# LAMEBOY.net
KiCad netlist of a schematic drawn in EAGLE
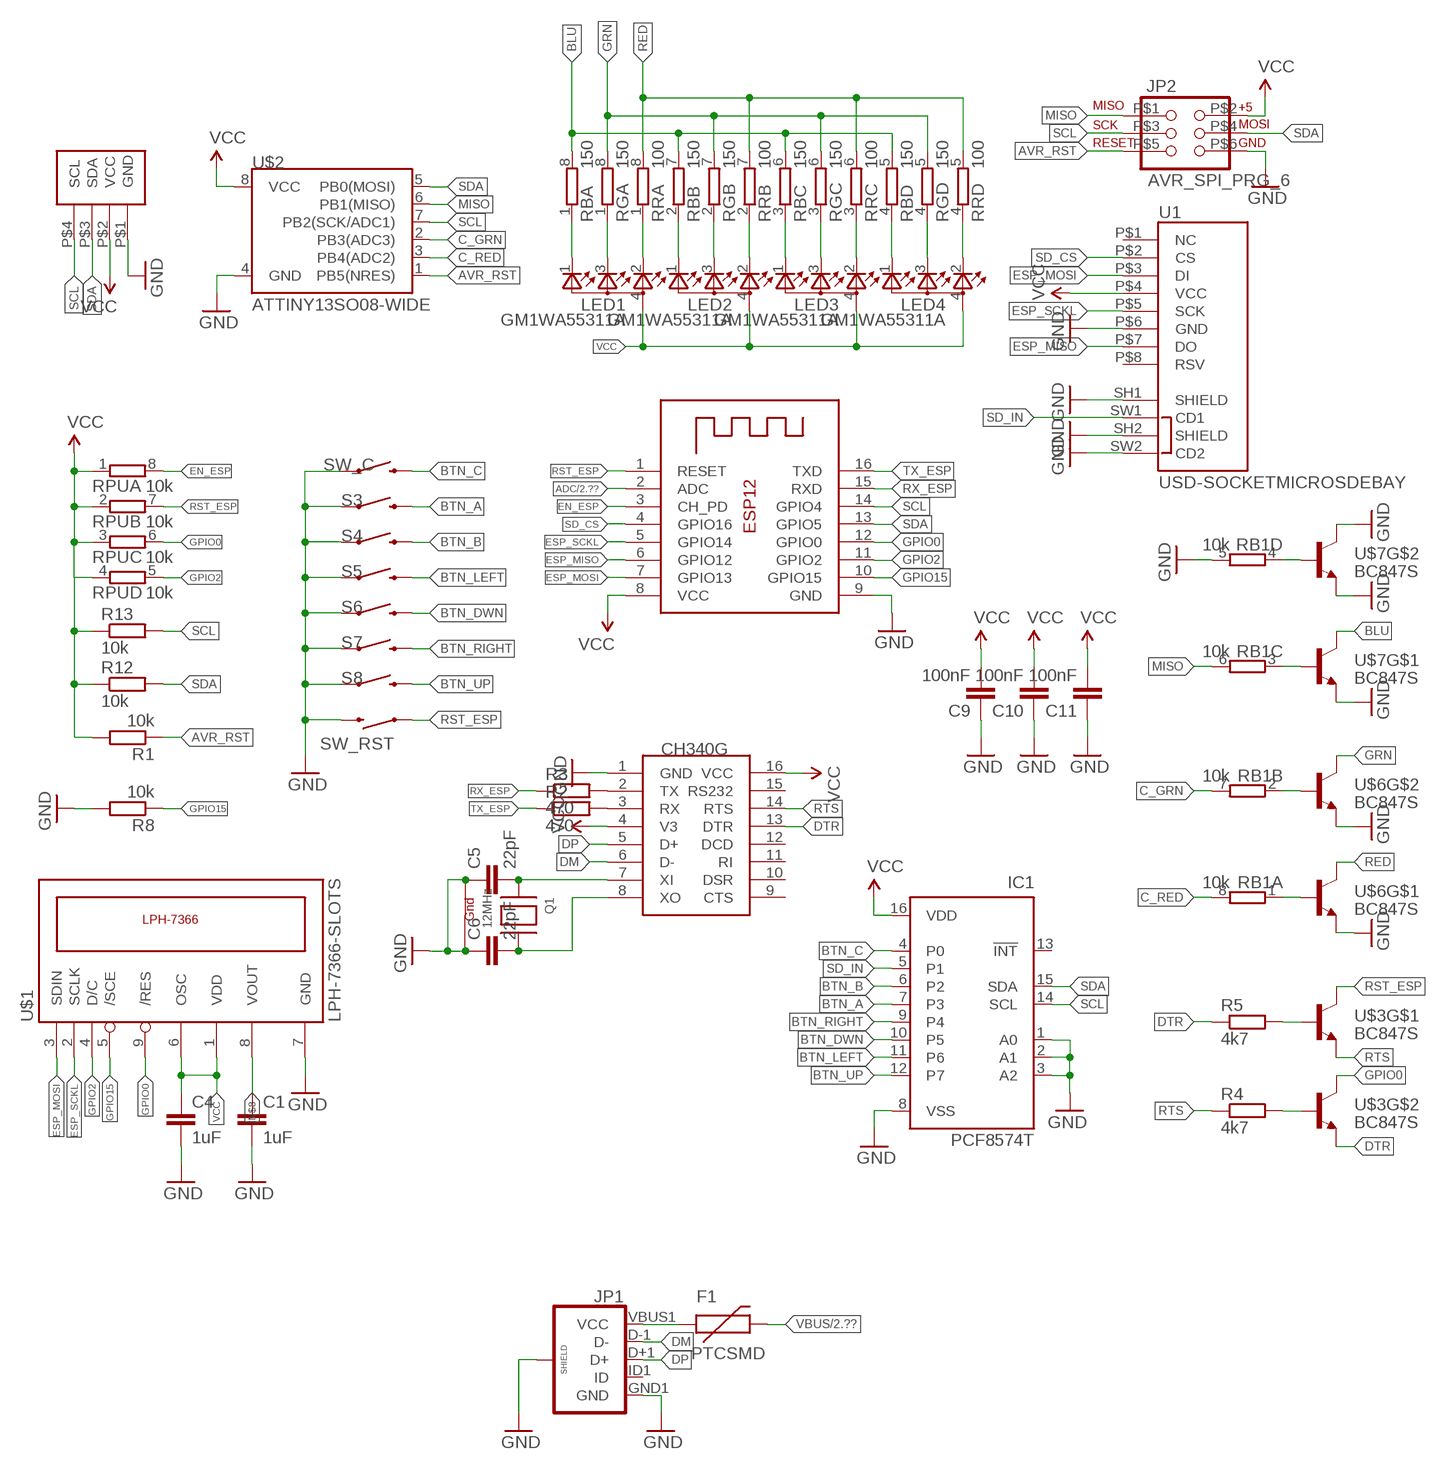
[diagram p0: schematic, sheet 1]
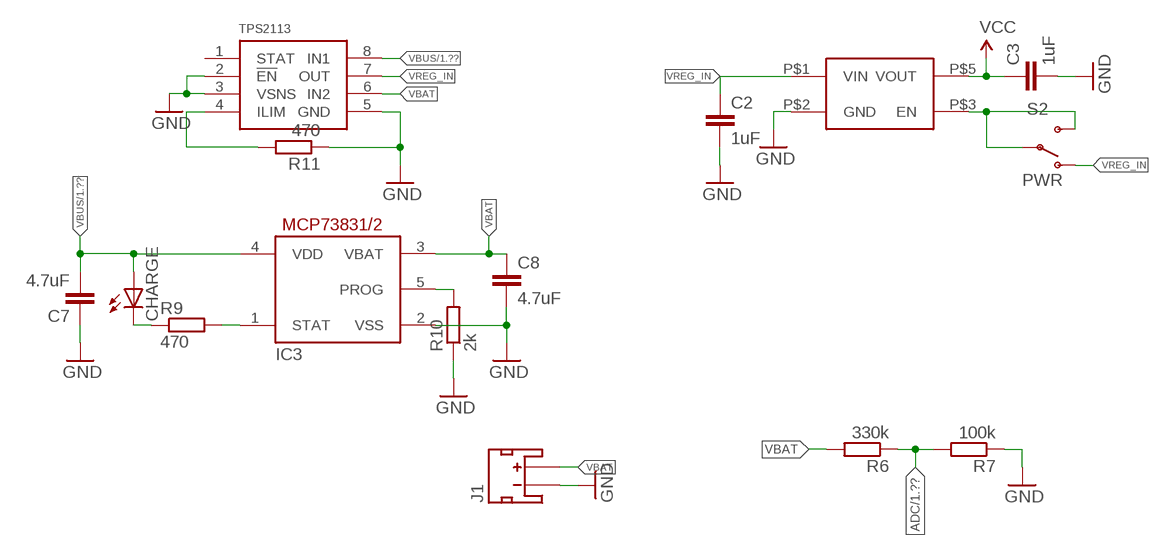
[diagram p1: schematic, sheet 2]

(export (version "E")
  (design (tool "Eeschema 10.0.6"))
  (components
    (comp (ref "C2")
      (value "1uF")
      (footprint "eagle-import:ONEFITSALL")
      (libsource (lib "eagle-import") (part "C-EUONEFITSALL"))
    )
    (comp (ref "C3")
      (value "1uF")
      (footprint "eagle-import:ONEFITSALL")
      (libsource (lib "eagle-import") (part "C-EUONEFITSALL"))
    )
    (comp (ref "C7")
      (value "4.7uF")
      (footprint "eagle-import:ONEFITSALL")
      (libsource (lib "eagle-import") (part "C-EUONEFITSALL"))
    )
    (comp (ref "C8")
      (value "4.7uF")
      (footprint "eagle-import:ONEFITSALL")
      (libsource (lib "eagle-import") (part "C-EUONEFITSALL"))
    )
    (comp (ref "CHARGE")
      (value "LEDCHARLIE")
      (footprint "eagle-import:CHIPLED_0603_CHARLIE")
      (libsource (lib "eagle-import") (part "LEDCHARLIE"))
    )
    (comp (ref "IC3")
      (value "MCP73831")
      (footprint "eagle-import:SOT23-5L")
      (libsource (lib "eagle-import") (part "MCP73831/OT"))
    )
    (comp (ref "J1")
      (value "JST_2MM_MALE")
      (footprint "eagle-import:JST-2-SMD")
      (libsource (lib "eagle-import") (part "JST_2MM_MALE"))
    )
    (comp (ref "R6")
      (value "330k")
      (footprint "eagle-import:ONEFITSALL")
      (libsource (lib "eagle-import") (part "R-EU_ONEFITSALL"))
    )
    (comp (ref "R7")
      (value "100k")
      (footprint "eagle-import:ONEFITSALL")
      (libsource (lib "eagle-import") (part "R-EU_ONEFITSALL"))
    )
    (comp (ref "R9")
      (value "470")
      (footprint "eagle-import:ONEFITSALL")
      (libsource (lib "eagle-import") (part "R-EU_ONEFITSALL"))
    )
    (comp (ref "R10")
      (value "2k")
      (footprint "eagle-import:ONEFITSALL")
      (libsource (lib "eagle-import") (part "R-EU_ONEFITSALL"))
    )
    (comp (ref "R11")
      (value "470")
      (footprint "eagle-import:ONEFITSALL")
      (libsource (lib "eagle-import") (part "R-EU_ONEFITSALL"))
    )
    (comp (ref "S2")
      (value "PWR")
      (footprint "eagle-import:SWITCH-SPST-SMD-A")
      (libsource (lib "eagle-import") (part "SWITCH-SPDT-SMD-A"))
    )
    (comp (ref "U$4")
      (value "TPS2113-PW")
      (footprint "eagle-import:TEXAS-PW")
      (libsource (lib "eagle-import") (part "TPS2113-PW"))
    )
    (comp (ref "U$9")
      (value "AP2112KAP2112K")
      (footprint "eagle-import:AP2112")
      (libsource (lib "eagle-import") (part "AP2112KAP2112K"))
    )
    (comp (ref "C1")
      (value "1uF")
      (footprint "eagle-import:ONEFITSALL")
      (libsource (lib "eagle-import") (part "C-EUONEFITSALL"))
    )
    (comp (ref "C4")
      (value "1uF")
      (footprint "eagle-import:ONEFITSALL")
      (libsource (lib "eagle-import") (part "C-EUONEFITSALL"))
    )
    (comp (ref "C5")
      (value "22pF")
      (footprint "eagle-import:ONEFITSALL")
      (libsource (lib "eagle-import") (part "C-EUONEFITSALL"))
    )
    (comp (ref "C6")
      (value "22pF")
      (footprint "eagle-import:ONEFITSALL")
      (libsource (lib "eagle-import") (part "C-EUONEFITSALL"))
    )
    (comp (ref "C9")
      (value "100nF")
      (footprint "eagle-import:ONEFITSALL")
      (libsource (lib "eagle-import") (part "C-EUONEFITSALL"))
    )
    (comp (ref "C10")
      (value "100nF")
      (footprint "eagle-import:ONEFITSALL")
      (libsource (lib "eagle-import") (part "C-EUONEFITSALL"))
    )
    (comp (ref "C11")
      (value "100nF")
      (footprint "eagle-import:ONEFITSALL")
      (libsource (lib "eagle-import") (part "C-EUONEFITSALL"))
    )
    (comp (ref "CH340G")
      (value "CH340GCH340G")
      (footprint "eagle-import:SOIC16")
      (libsource (lib "eagle-import") (part "CH340GCH340G"))
    )
    (comp (ref "F1")
      (value "PTCSMD")
      (footprint "eagle-import:PTC-1206")
      (libsource (lib "eagle-import") (part "PTCSMD"))
    )
    (comp (ref "IC1")
      (value "PCF8574T")
      (footprint "eagle-import:SO16W")
      (fields (field (name "MPN") "PCF8574T/3,512"))
      (libsource (lib "eagle-import") (part "PCF8574T"))
    )
    (comp (ref "JP1")
      (value "USB_MICROB_PLUG-IDK")
      (footprint "eagle-import:USB-AB-MICRO-SMD_SLOT")
      (libsource (lib "eagle-import") (part "USB_MICROB_PLUG-IDK"))
    )
    (comp (ref "JP2")
      (value "AVR_SPI_PRG_6")
      (footprint "eagle-import:2X3_SMD_PAD")
      (libsource (lib "eagle-import") (part "AVR_SPI_PRG_6"))
    )
    (comp (ref "LED1")
      (value "GM1WA55311A")
      (footprint "eagle-import:GM1WA55311A")
      (libsource (lib "eagle-import") (part "GM1WA55311A"))
    )
    (comp (ref "LED2")
      (value "GM1WA55311A")
      (footprint "eagle-import:GM1WA55311A")
      (libsource (lib "eagle-import") (part "GM1WA55311A"))
    )
    (comp (ref "LED3")
      (value "GM1WA55311A")
      (footprint "eagle-import:GM1WA55311A")
      (libsource (lib "eagle-import") (part "GM1WA55311A"))
    )
    (comp (ref "LED4")
      (value "GM1WA55311A")
      (footprint "eagle-import:GM1WA55311A")
      (libsource (lib "eagle-import") (part "GM1WA55311A"))
    )
    (comp (ref "Q1")
      (value "12MHz")
      (footprint "eagle-import:NX3225_BIGGER")
      (libsource (lib "eagle-import") (part "XTAL-4BIGGER"))
    )
    (comp (ref "R1")
      (value "10k")
      (footprint "eagle-import:ONEFITSALL")
      (libsource (lib "eagle-import") (part "R-EU_ONEFITSALL"))
    )
    (comp (ref "R2")
      (value "470")
      (footprint "eagle-import:ONEFITSALL")
      (libsource (lib "eagle-import") (part "R-EU_ONEFITSALL"))
    )
    (comp (ref "R3")
      (value "470")
      (footprint "eagle-import:ONEFITSALL")
      (libsource (lib "eagle-import") (part "R-EU_ONEFITSALL"))
    )
    (comp (ref "R4")
      (value "4k7")
      (footprint "eagle-import:ONEFITSALL")
      (libsource (lib "eagle-import") (part "R-EU_ONEFITSALL"))
    )
    (comp (ref "R5")
      (value "4k7")
      (footprint "eagle-import:ONEFITSALL")
      (libsource (lib "eagle-import") (part "R-EU_ONEFITSALL"))
    )
    (comp (ref "R8")
      (value "10k")
      (footprint "eagle-import:ONEFITSALL")
      (libsource (lib "eagle-import") (part "R-EU_ONEFITSALL"))
    )
    (comp (ref "R12")
      (value "10k")
      (footprint "eagle-import:ONEFITSALL")
      (libsource (lib "eagle-import") (part "R-EU_ONEFITSALL"))
    )
    (comp (ref "R13")
      (value "10k")
      (footprint "eagle-import:ONEFITSALL")
      (libsource (lib "eagle-import") (part "R-EU_ONEFITSALL"))
    )
    (comp (ref "RB")
      (value "150")
      (footprint "eagle-import:0603-ARC")
      (libsource (lib "eagle-import") (part "4R-N0603-ARC"))
    )
    (comp (ref "RB1")
      (value "10k")
      (footprint "eagle-import:0603-ARC")
      (libsource (lib "eagle-import") (part "4R-N0603-ARC"))
    )
    (comp (ref "RG")
      (value "150")
      (footprint "eagle-import:0603-ARC")
      (libsource (lib "eagle-import") (part "4R-N0603-ARC"))
    )
    (comp (ref "RPU")
      (value "10k")
      (footprint "eagle-import:0603-ARC")
      (libsource (lib "eagle-import") (part "4R-N0603-ARC"))
    )
    (comp (ref "RR")
      (value "100")
      (footprint "eagle-import:0603-ARC")
      (libsource (lib "eagle-import") (part "4R-N0603-ARC"))
    )
    (comp (ref "S3")
      (value "SWITCH-MOMENTARY-2SMD-4")
      (footprint "eagle-import:TACTILE_SWITCH_TALL")
      (libsource (lib "eagle-import") (part "SWITCH-MOMENTARY-2SMD-4"))
    )
    (comp (ref "S4")
      (value "SWITCH-MOMENTARY-2SMD-4")
      (footprint "eagle-import:TACTILE_SWITCH_TALL")
      (libsource (lib "eagle-import") (part "SWITCH-MOMENTARY-2SMD-4"))
    )
    (comp (ref "S5")
      (value "SWITCH-MOMENTARY-2SMD-4")
      (footprint "eagle-import:TACTILE_SWITCH_TALL")
      (libsource (lib "eagle-import") (part "SWITCH-MOMENTARY-2SMD-4"))
    )
    (comp (ref "S6")
      (value "SWITCH-MOMENTARY-2SMD-4")
      (footprint "eagle-import:TACTILE_SWITCH_TALL")
      (libsource (lib "eagle-import") (part "SWITCH-MOMENTARY-2SMD-4"))
    )
    (comp (ref "S7")
      (value "SWITCH-MOMENTARY-2SMD-4")
      (footprint "eagle-import:TACTILE_SWITCH_TALL")
      (libsource (lib "eagle-import") (part "SWITCH-MOMENTARY-2SMD-4"))
    )
    (comp (ref "S8")
      (value "SWITCH-MOMENTARY-2SMD-4")
      (footprint "eagle-import:TACTILE_SWITCH_TALL")
      (libsource (lib "eagle-import") (part "SWITCH-MOMENTARY-2SMD-4"))
    )
    (comp (ref "SW_C")
      (value "SWITCH-MOMENTARY-2-SMD-1101NE")
      (footprint "eagle-import:TACTILE-SWITCH-1101NE")
      (libsource (lib "eagle-import") (part "SWITCH-MOMENTARY-2-SMD-1101NE"))
    )
    (comp (ref "SW_RST")
      (value "SWITCH-MOMENTARY-2-SMD-1101NE")
      (footprint "eagle-import:TACTILE-SWITCH-1101NE")
      (libsource (lib "eagle-import") (part "SWITCH-MOMENTARY-2-SMD-1101NE"))
    )
    (comp (ref "U$1")
      (value "LPH-7366-SLOTS")
      (footprint "eagle-import:LPH-7366-SLOTS")
      (libsource (lib "eagle-import") (part "LPH-7366-SLOTS"))
    )
    (comp (ref "U$2")
      (value "ATTINY13SO08-WIDE")
      (footprint "eagle-import:SO08-EIAJ")
      (libsource (lib "eagle-import") (part "ATTINY13SO08-WIDE"))
    )
    (comp (ref "U$3")
      (value "BC847S")
      (footprint "eagle-import:SOT363")
      (libsource (lib "eagle-import") (part "MMDT3904"))
    )
    (comp (ref "U$6")
      (value "BC847S")
      (footprint "eagle-import:SOT363")
      (libsource (lib "eagle-import") (part "MMDT3904"))
    )
    (comp (ref "U$7")
      (value "BC847S")
      (footprint "eagle-import:SOT363")
      (libsource (lib "eagle-import") (part "MMDT3904"))
    )
    (comp (ref "U$10")
      (value "I2C_GROVE")
      (footprint "eagle-import:I2C_GROVE")
      (libsource (lib "eagle-import") (part "I2C_GROVE"))
    )
    (comp (ref "U1")
      (value "USD-SOCKETMICROSDEBAY")
      (footprint "eagle-import:MICRO-SD-SOCKET-EBAY")
      (libsource (lib "eagle-import") (part "USD-SOCKETMICROSDEBAY"))
    )
    (comp (ref "X1")
      (value "ESP-12")
      (footprint "eagle-import:ESP-12")
      (libsource (lib "eagle-import") (part "ESP-12"))
    )
  )
  (nets
    (net (code "1") (name "ADC") (class "Default")
      (node (ref "R6") (pin "P$1") (pinfunction "1_P$1") (pintype "passive"))
      (node (ref "R7") (pin "P$2") (pinfunction "2_P$2") (pintype "passive"))
      (node (ref "X1") (pin "2") (pinfunction "ADC_2") (pintype "passive"))
    )
    (net (code "2") (name "AVR_RST") (class "Default")
      (node (ref "JP2") (pin "P$5") (pinfunction "5_P$5") (pintype "passive"))
      (node (ref "R1") (pin "P$1") (pinfunction "1_P$1") (pintype "passive"))
      (node (ref "U$2") (pin "1") (pinfunction "PB5(NRES)_1") (pintype "bidirectional"))
    )
    (net (code "3") (name "BLU") (class "Default")
      (node (ref "RB") (pin "5") (pinfunction "2_5") (pintype "passive"))
      (node (ref "RB") (pin "6") (pinfunction "2_6") (pintype "passive"))
      (node (ref "RB") (pin "7") (pinfunction "2_7") (pintype "passive"))
      (node (ref "RB") (pin "8") (pinfunction "2_8") (pintype "passive"))
      (node (ref "U$7") (pin "3") (pinfunction "C_3") (pintype "passive"))
    )
    (net (code "4") (name "BTN_A") (class "Default")
      (node (ref "IC1") (pin "7") (pinfunction "P3_7") (pintype "bidirectional"))
      (node (ref "S3") (pin "B2") (pinfunction "2_B2") (pintype "passive"))
    )
    (net (code "5") (name "BTN_B") (class "Default")
      (node (ref "IC1") (pin "6") (pinfunction "P2_6") (pintype "bidirectional"))
      (node (ref "S4") (pin "B2") (pinfunction "2_B2") (pintype "passive"))
    )
    (net (code "6") (name "BTN_C") (class "Default")
      (node (ref "IC1") (pin "4") (pinfunction "P0_4") (pintype "bidirectional"))
      (node (ref "SW_C") (pin "P$2") (pinfunction "2_P$2") (pintype "passive"))
    )
    (net (code "7") (name "BTN_DWN") (class "Default")
      (node (ref "IC1") (pin "10") (pinfunction "P5_10") (pintype "bidirectional"))
      (node (ref "S6") (pin "B2") (pinfunction "2_B2") (pintype "passive"))
    )
    (net (code "8") (name "BTN_LEFT") (class "Default")
      (node (ref "IC1") (pin "11") (pinfunction "P6_11") (pintype "bidirectional"))
      (node (ref "S5") (pin "B2") (pinfunction "2_B2") (pintype "passive"))
    )
    (net (code "9") (name "BTN_RIGHT") (class "Default")
      (node (ref "IC1") (pin "9") (pinfunction "P4_9") (pintype "bidirectional"))
      (node (ref "S7") (pin "B2") (pinfunction "2_B2") (pintype "passive"))
    )
    (net (code "10") (name "BTN_UP") (class "Default")
      (node (ref "IC1") (pin "12") (pinfunction "P7_12") (pintype "bidirectional"))
      (node (ref "S8") (pin "B2") (pinfunction "2_B2") (pintype "passive"))
    )
    (net (code "11") (name "C_GRN") (class "Default")
      (node (ref "RB1") (pin "7") (pinfunction "2_7") (pintype "passive"))
      (node (ref "U$2") (pin "2") (pinfunction "PB3(ADC3)_2") (pintype "bidirectional"))
    )
    (net (code "12") (name "C_RED") (class "Default")
      (node (ref "RB1") (pin "8") (pinfunction "2_8") (pintype "passive"))
      (node (ref "U$2") (pin "3") (pinfunction "PB4(ADC2)_3") (pintype "bidirectional"))
    )
    (net (code "13") (name "DM") (class "Default")
      (node (ref "CH340G") (pin "6") (pinfunction "D-_6") (pintype "bidirectional"))
      (node (ref "JP1") (pin "D-1") (pinfunction "D-_D-1") (pintype "bidirectional"))
    )
    (net (code "14") (name "DP") (class "Default")
      (node (ref "CH340G") (pin "5") (pinfunction "D+_5") (pintype "bidirectional"))
      (node (ref "JP1") (pin "D+1") (pinfunction "D+_D+1") (pintype "bidirectional"))
    )
    (net (code "15") (name "DTR") (class "Default")
      (node (ref "CH340G") (pin "13") (pinfunction "DTR_13") (pintype "bidirectional"))
      (node (ref "R5") (pin "P$1") (pinfunction "1_P$1") (pintype "passive"))
      (node (ref "U$3") (pin "1") (pinfunction "E_1") (pintype "passive"))
    )
    (net (code "16") (name "EN_ESP") (class "Default")
      (node (ref "RPU") (pin "8") (pinfunction "2_8") (pintype "passive"))
      (node (ref "X1") (pin "3") (pinfunction "CH_PD_3") (pintype "input"))
    )
    (net (code "17") (name "ESP_MISO") (class "Default")
      (node (ref "U1") (pin "P$7") (pinfunction "DO_P$7") (pintype "bidirectional"))
      (node (ref "X1") (pin "6") (pinfunction "GPIO12_6") (pintype "bidirectional"))
    )
    (net (code "18") (name "ESP_MOSI") (class "Default")
      (node (ref "U$1") (pin "3") (pinfunction "SDIN_3") (pintype "input"))
      (node (ref "U1") (pin "P$3") (pinfunction "DI_P$3") (pintype "bidirectional"))
      (node (ref "X1") (pin "7") (pinfunction "GPIO13_7") (pintype "bidirectional"))
    )
    (net (code "19") (name "ESP_SCKL") (class "Default")
      (node (ref "U$1") (pin "2") (pinfunction "SCLK_2") (pintype "input"))
      (node (ref "U1") (pin "P$5") (pinfunction "SCK_P$5") (pintype "bidirectional"))
      (node (ref "X1") (pin "5") (pinfunction "GPIO14_5") (pintype "bidirectional"))
    )
    (net (code "20") (name "GND") (class "Default")
      (node (ref "C1") (pin "P$2") (pinfunction "2_P$2") (pintype "passive"))
      (node (ref "C10") (pin "P$1") (pinfunction "1_P$1") (pintype "passive"))
      (node (ref "C11") (pin "P$1") (pinfunction "1_P$1") (pintype "passive"))
      (node (ref "C2") (pin "P$2") (pinfunction "2_P$2") (pintype "passive"))
      (node (ref "C3") (pin "P$2") (pinfunction "2_P$2") (pintype "passive"))
      (node (ref "C4") (pin "P$2") (pinfunction "2_P$2") (pintype "passive"))
      (node (ref "C5") (pin "P$1") (pinfunction "1_P$1") (pintype "passive"))
      (node (ref "C6") (pin "P$1") (pinfunction "1_P$1") (pintype "passive"))
      (node (ref "C7") (pin "P$1") (pinfunction "1_P$1") (pintype "passive"))
      (node (ref "C8") (pin "P$2") (pinfunction "2_P$2") (pintype "passive"))
      (node (ref "C9") (pin "P$1") (pinfunction "1_P$1") (pintype "passive"))
      (node (ref "CH340G") (pin "1") (pinfunction "GND_1") (pintype "bidirectional"))
      (node (ref "IC1") (pin "1") (pinfunction "A0_1") (pintype "input"))
      (node (ref "IC1") (pin "2") (pinfunction "A1_2") (pintype "input"))
      (node (ref "IC1") (pin "3") (pinfunction "A2_3") (pintype "input"))
      (node (ref "IC1") (pin "8") (pinfunction "VSS_8") (pintype "power_in"))
      (node (ref "IC3") (pin "2") (pinfunction "VSS_2") (pintype "power_in"))
      (node (ref "J1") (pin "1") (pinfunction "-_1") (pintype "bidirectional"))
      (node (ref "JP1") (pin "GND1") (pinfunction "GND_GND1") (pintype "bidirectional"))
      (node (ref "JP1") (pin "P$1") (pinfunction "SHIELD_P$1") (pintype "bidirectional"))
      (node (ref "JP1") (pin "P$2") (pinfunction "SHIELD_P$2") (pintype "bidirectional"))
      (node (ref "JP1") (pin "P$3") (pinfunction "SHIELD_P$3") (pintype "bidirectional"))
      (node (ref "JP1") (pin "P$4") (pinfunction "SHIELD_P$4") (pintype "bidirectional"))
      (node (ref "JP2") (pin "P$6") (pinfunction "6_P$6") (pintype "passive"))
      (node (ref "Q1") (pin "2") (pinfunction "G2_2") (pintype "power_in"))
      (node (ref "Q1") (pin "4") (pinfunction "G1_4") (pintype "power_in"))
      (node (ref "R10") (pin "P$1") (pinfunction "1_P$1") (pintype "passive"))
      (node (ref "R11") (pin "P$1") (pinfunction "1_P$1") (pintype "passive"))
      (node (ref "R7") (pin "P$1") (pinfunction "1_P$1") (pintype "passive"))
      (node (ref "R8") (pin "P$2") (pinfunction "2_P$2") (pintype "passive"))
      (node (ref "RB1") (pin "5") (pinfunction "2_5") (pintype "passive"))
      (node (ref "S3") (pin "A2") (pinfunction "1_A2") (pintype "passive"))
      (node (ref "S4") (pin "A2") (pinfunction "1_A2") (pintype "passive"))
      (node (ref "S5") (pin "A2") (pinfunction "1_A2") (pintype "passive"))
      (node (ref "S6") (pin "A2") (pinfunction "1_A2") (pintype "passive"))
      (node (ref "S7") (pin "A2") (pinfunction "1_A2") (pintype "passive"))
      (node (ref "S8") (pin "A2") (pinfunction "1_A2") (pintype "passive"))
      (node (ref "SW_C") (pin "P$1") (pinfunction "1_P$1") (pintype "passive"))
      (node (ref "SW_RST") (pin "P$2") (pinfunction "2_P$2") (pintype "passive"))
      (node (ref "U$1") (pin "7") (pinfunction "GND_7") (pintype "power_in"))
      (node (ref "U$10") (pin "P$1") (pinfunction "GND_P$1") (pintype "bidirectional"))
      (node (ref "U$2") (pin "4") (pinfunction "GND_4") (pintype "bidirectional"))
      (node (ref "U$4") (pin "2") (pinfunction "~{EN}_2") (pintype "bidirectional"))
      (node (ref "U$4") (pin "3") (pinfunction "VSNS_3") (pintype "bidirectional"))
      (node (ref "U$4") (pin "5") (pinfunction "GND_5") (pintype "bidirectional"))
      (node (ref "U$6") (pin "1") (pinfunction "E_1") (pintype "passive"))
      (node (ref "U$6") (pin "4") (pinfunction "E_4") (pintype "passive"))
      (node (ref "U$7") (pin "1") (pinfunction "E_1") (pintype "passive"))
      (node (ref "U$7") (pin "4") (pinfunction "E_4") (pintype "passive"))
      (node (ref "U$7") (pin "6") (pinfunction "C_6") (pintype "passive"))
      (node (ref "U$9") (pin "P$2") (pinfunction "GND_P$2") (pintype "bidirectional"))
      (node (ref "U1") (pin "P$6") (pinfunction "GND_P$6") (pintype "bidirectional"))
      (node (ref "U1") (pin "SH1") (pinfunction "SHIELD_SH1") (pintype "bidirectional"))
      (node (ref "U1") (pin "SH2") (pinfunction "SHIELD_SH2") (pintype "bidirectional"))
      (node (ref "U1") (pin "SW2") (pinfunction "CD2_SW2") (pintype "bidirectional"))
      (node (ref "X1") (pin "9") (pinfunction "GND_9") (pintype "power_in"))
    )
    (net (code "21") (name "GPIO0") (class "Default")
      (node (ref "RPU") (pin "6") (pinfunction "2_6") (pintype "passive"))
      (node (ref "U$1") (pin "9") (pinfunction "/RES_9") (pintype "input"))
      (node (ref "U$3") (pin "6") (pinfunction "C_6") (pintype "passive"))
      (node (ref "X1") (pin "12") (pinfunction "GPIO0_12") (pintype "bidirectional"))
    )
    (net (code "22") (name "GPIO2") (class "Default")
      (node (ref "RPU") (pin "5") (pinfunction "2_5") (pintype "passive"))
      (node (ref "U$1") (pin "4") (pinfunction "D/C_4") (pintype "input"))
      (node (ref "X1") (pin "11") (pinfunction "GPIO2_11") (pintype "bidirectional"))
    )
    (net (code "23") (name "GPIO15") (class "Default")
      (node (ref "R8") (pin "P$1") (pinfunction "1_P$1") (pintype "passive"))
      (node (ref "U$1") (pin "5") (pinfunction "/SCE_5") (pintype "input"))
      (node (ref "X1") (pin "10") (pinfunction "GPIO15_10") (pintype "bidirectional"))
    )
    (net (code "24") (name "GRN") (class "Default")
      (node (ref "RG") (pin "5") (pinfunction "2_5") (pintype "passive"))
      (node (ref "RG") (pin "6") (pinfunction "2_6") (pintype "passive"))
      (node (ref "RG") (pin "7") (pinfunction "2_7") (pintype "passive"))
      (node (ref "RG") (pin "8") (pinfunction "2_8") (pintype "passive"))
      (node (ref "U$6") (pin "6") (pinfunction "C_6") (pintype "passive"))
    )
    (net (code "25") (name "MISO") (class "Default")
      (node (ref "JP2") (pin "P$1") (pinfunction "1_P$1") (pintype "passive"))
      (node (ref "RB1") (pin "6") (pinfunction "2_6") (pintype "passive"))
      (node (ref "U$2") (pin "6") (pinfunction "PB1(MISO)_6") (pintype "bidirectional"))
    )
    (net (code "26") (name "N$8") (class "Default")
      (node (ref "C1") (pin "P$1") (pinfunction "1_P$1") (pintype "passive"))
      (node (ref "U$1") (pin "8") (pinfunction "VOUT_8") (pintype "passive"))
    )
    (net (code "27") (name "Net-(C5-2)") (class "Default")
      (node (ref "C5") (pin "P$2") (pinfunction "2_P$2") (pintype "passive"))
      (node (ref "CH340G") (pin "7") (pinfunction "XI_7") (pintype "bidirectional"))
      (node (ref "Q1") (pin "1") (pinfunction "X1_1") (pintype "bidirectional"))
    )
    (net (code "28") (name "Net-(C6-2)") (class "Default")
      (node (ref "C6") (pin "P$2") (pinfunction "2_P$2") (pintype "passive"))
      (node (ref "CH340G") (pin "8") (pinfunction "XO_8") (pintype "bidirectional"))
      (node (ref "Q1") (pin "3") (pinfunction "X2_3") (pintype "bidirectional"))
    )
    (net (code "29") (name "Net-(CH340G-RX)") (class "Default")
      (node (ref "CH340G") (pin "3") (pinfunction "RX_3") (pintype "bidirectional"))
      (node (ref "R2") (pin "P$2") (pinfunction "2_P$2") (pintype "passive"))
    )
    (net (code "30") (name "Net-(CH340G-TX)") (class "Default")
      (node (ref "CH340G") (pin "2") (pinfunction "TX_2") (pintype "bidirectional"))
      (node (ref "R3") (pin "P$2") (pinfunction "2_P$2") (pintype "passive"))
    )
    (net (code "31") (name "Net-(IC3-PROG)") (class "Default")
      (node (ref "IC3") (pin "5") (pinfunction "PROG_5") (pintype "input"))
      (node (ref "R10") (pin "P$2") (pinfunction "2_P$2") (pintype "passive"))
    )
    (net (code "32") (name "Net-(IC3-STAT)") (class "Default")
      (node (ref "IC3") (pin "1") (pinfunction "STAT_1") (pintype "output"))
      (node (ref "R9") (pin "P$2") (pinfunction "2_P$2") (pintype "passive"))
    )
    (net (code "33") (name "Net-(JP1-VCC)") (class "Default")
      (node (ref "F1") (pin "1") (pinfunction "1_1") (pintype "bidirectional"))
      (node (ref "JP1") (pin "VBUS1") (pinfunction "VCC_VBUS1") (pintype "bidirectional"))
    )
    (net (code "34") (name "Net-(LED1-CBLUE)") (class "Default")
      (node (ref "LED1") (pin "3") (pinfunction "CBLUE_3") (pintype "passive"))
      (node (ref "RG") (pin "1") (pinfunction "1_1") (pintype "passive"))
    )
    (net (code "35") (name "Net-(LED1-CGREEN)") (class "Default")
      (node (ref "LED1") (pin "1") (pinfunction "CGREEN_1") (pintype "passive"))
      (node (ref "RB") (pin "1") (pinfunction "1_1") (pintype "passive"))
    )
    (net (code "36") (name "Net-(LED1-CRED)") (class "Default")
      (node (ref "LED1") (pin "2") (pinfunction "CRED_2") (pintype "passive"))
      (node (ref "RR") (pin "1") (pinfunction "1_1") (pintype "passive"))
    )
    (net (code "37") (name "Net-(LED2-CBLUE)") (class "Default")
      (node (ref "LED2") (pin "3") (pinfunction "CBLUE_3") (pintype "passive"))
      (node (ref "RG") (pin "2") (pinfunction "1_2") (pintype "passive"))
    )
    (net (code "38") (name "Net-(LED2-CGREEN)") (class "Default")
      (node (ref "LED2") (pin "1") (pinfunction "CGREEN_1") (pintype "passive"))
      (node (ref "RB") (pin "2") (pinfunction "1_2") (pintype "passive"))
    )
    (net (code "39") (name "Net-(LED2-CRED)") (class "Default")
      (node (ref "LED2") (pin "2") (pinfunction "CRED_2") (pintype "passive"))
      (node (ref "RR") (pin "2") (pinfunction "1_2") (pintype "passive"))
    )
    (net (code "40") (name "Net-(LED3-CBLUE)") (class "Default")
      (node (ref "LED3") (pin "3") (pinfunction "CBLUE_3") (pintype "passive"))
      (node (ref "RG") (pin "3") (pinfunction "1_3") (pintype "passive"))
    )
    (net (code "41") (name "Net-(LED3-CGREEN)") (class "Default")
      (node (ref "LED3") (pin "1") (pinfunction "CGREEN_1") (pintype "passive"))
      (node (ref "RB") (pin "3") (pinfunction "1_3") (pintype "passive"))
    )
    (net (code "42") (name "Net-(LED3-CRED)") (class "Default")
      (node (ref "LED3") (pin "2") (pinfunction "CRED_2") (pintype "passive"))
      (node (ref "RR") (pin "3") (pinfunction "1_3") (pintype "passive"))
    )
    (net (code "43") (name "Net-(LED4-CBLUE)") (class "Default")
      (node (ref "LED4") (pin "3") (pinfunction "CBLUE_3") (pintype "passive"))
      (node (ref "RG") (pin "4") (pinfunction "1_4") (pintype "passive"))
    )
    (net (code "44") (name "Net-(LED4-CGREEN)") (class "Default")
      (node (ref "LED4") (pin "1") (pinfunction "CGREEN_1") (pintype "passive"))
      (node (ref "RB") (pin "4") (pinfunction "1_4") (pintype "passive"))
    )
    (net (code "45") (name "Net-(LED4-CRED)") (class "Default")
      (node (ref "LED4") (pin "2") (pinfunction "CRED_2") (pintype "passive"))
      (node (ref "RR") (pin "4") (pinfunction "1_4") (pintype "passive"))
    )
    (net (code "46") (name "Net-(R4-2)") (class "Default")
      (node (ref "R4") (pin "P$2") (pinfunction "2_P$2") (pintype "passive"))
      (node (ref "U$3") (pin "2") (pinfunction "B_2") (pintype "passive"))
    )
    (net (code "47") (name "Net-(R5-2)") (class "Default")
      (node (ref "R5") (pin "P$2") (pinfunction "2_P$2") (pintype "passive"))
      (node (ref "U$3") (pin "5") (pinfunction "B_5") (pintype "passive"))
    )
    (net (code "48") (name "Net-(R9-1)") (class "Default")
      (node (ref "CHARGE") (pin "C") (pinfunction "C_C") (pintype "passive"))
      (node (ref "R9") (pin "P$1") (pinfunction "1_P$1") (pintype "passive"))
    )
    (net (code "49") (name "Net-(R11-2)") (class "Default")
      (node (ref "R11") (pin "P$2") (pinfunction "2_P$2") (pintype "passive"))
      (node (ref "U$4") (pin "4") (pinfunction "ILIM_4") (pintype "bidirectional"))
    )
    (net (code "50") (name "Net-(RB1B-1)") (class "Default")
      (node (ref "RB1") (pin "2") (pinfunction "1_2") (pintype "passive"))
      (node (ref "U$6") (pin "2") (pinfunction "B_2") (pintype "passive"))
    )
    (net (code "51") (name "Net-(RB1C-1)") (class "Default")
      (node (ref "RB1") (pin "3") (pinfunction "1_3") (pintype "passive"))
      (node (ref "U$7") (pin "5") (pinfunction "B_5") (pintype "passive"))
    )
    (net (code "52") (name "Net-(RB1D-1)") (class "Default")
      (node (ref "RB1") (pin "4") (pinfunction "1_4") (pintype "passive"))
      (node (ref "U$7") (pin "2") (pinfunction "B_2") (pintype "passive"))
    )
    (net (code "53") (name "Net-(S2-P)") (class "Default")
      (node (ref "S2") (pin "2") (pinfunction "P_2") (pintype "passive"))
      (node (ref "S2") (pin "3") (pinfunction "S_3") (pintype "passive"))
      (node (ref "U$9") (pin "P$3") (pinfunction "EN_P$3") (pintype "bidirectional"))
    )
    (net (code "54") (name "Net-(U$6A-B)") (class "Default")
      (node (ref "RB1") (pin "1") (pinfunction "1_1") (pintype "passive"))
      (node (ref "U$6") (pin "5") (pinfunction "B_5") (pintype "passive"))
    )
    (net (code "55") (name "RED") (class "Default")
      (node (ref "RR") (pin "5") (pinfunction "2_5") (pintype "passive"))
      (node (ref "RR") (pin "6") (pinfunction "2_6") (pintype "passive"))
      (node (ref "RR") (pin "7") (pinfunction "2_7") (pintype "passive"))
      (node (ref "RR") (pin "8") (pinfunction "2_8") (pintype "passive"))
      (node (ref "U$6") (pin "3") (pinfunction "C_3") (pintype "passive"))
    )
    (net (code "56") (name "RST_ESP") (class "Default")
      (node (ref "RPU") (pin "7") (pinfunction "2_7") (pintype "passive"))
      (node (ref "SW_RST") (pin "P$1") (pinfunction "1_P$1") (pintype "passive"))
      (node (ref "U$3") (pin "3") (pinfunction "C_3") (pintype "passive"))
      (node (ref "X1") (pin "1") (pinfunction "RESET_1") (pintype "input"))
    )
    (net (code "57") (name "RTS") (class "Default")
      (node (ref "CH340G") (pin "14") (pinfunction "RTS_14") (pintype "bidirectional"))
      (node (ref "R4") (pin "P$1") (pinfunction "1_P$1") (pintype "passive"))
      (node (ref "U$3") (pin "4") (pinfunction "E_4") (pintype "passive"))
    )
    (net (code "58") (name "RX_ESP") (class "Default")
      (node (ref "R3") (pin "P$1") (pinfunction "1_P$1") (pintype "passive"))
      (node (ref "X1") (pin "15") (pinfunction "RXD_15") (pintype "input"))
    )
    (net (code "59") (name "SCL") (class "Default")
      (node (ref "IC1") (pin "14") (pinfunction "SCL_14") (pintype "input"))
      (node (ref "JP2") (pin "P$3") (pinfunction "3_P$3") (pintype "passive"))
      (node (ref "R13") (pin "P$2") (pinfunction "2_P$2") (pintype "passive"))
      (node (ref "U$10") (pin "P$4") (pinfunction "SCL_P$4") (pintype "bidirectional"))
      (node (ref "U$2") (pin "7") (pinfunction "PB2(SCK/ADC1)_7") (pintype "bidirectional"))
      (node (ref "X1") (pin "14") (pinfunction "GPIO4_14") (pintype "bidirectional"))
    )
    (net (code "60") (name "SDA") (class "Default")
      (node (ref "IC1") (pin "15") (pinfunction "SDA_15") (pintype "bidirectional"))
      (node (ref "JP2") (pin "P$4") (pinfunction "4_P$4") (pintype "passive"))
      (node (ref "R12") (pin "P$2") (pinfunction "2_P$2") (pintype "passive"))
      (node (ref "U$10") (pin "P$3") (pinfunction "SDA_P$3") (pintype "bidirectional"))
      (node (ref "U$2") (pin "5") (pinfunction "PB0(MOSI)_5") (pintype "bidirectional"))
      (node (ref "X1") (pin "13") (pinfunction "GPIO5_13") (pintype "bidirectional"))
    )
    (net (code "61") (name "SD_CS") (class "Default")
      (node (ref "U1") (pin "P$2") (pinfunction "CS_P$2") (pintype "bidirectional"))
      (node (ref "X1") (pin "4") (pinfunction "GPIO16_4") (pintype "bidirectional"))
    )
    (net (code "62") (name "SD_IN") (class "Default")
      (node (ref "IC1") (pin "5") (pinfunction "P1_5") (pintype "bidirectional"))
      (node (ref "U1") (pin "SW1") (pinfunction "CD1_SW1") (pintype "bidirectional"))
    )
    (net (code "63") (name "TX_ESP") (class "Default")
      (node (ref "R2") (pin "P$1") (pinfunction "1_P$1") (pintype "passive"))
      (node (ref "X1") (pin "16") (pinfunction "TXD_16") (pintype "output"))
    )
    (net (code "64") (name "VBAT") (class "Default")
      (node (ref "C8") (pin "P$1") (pinfunction "1_P$1") (pintype "passive"))
      (node (ref "IC3") (pin "3") (pinfunction "VBAT_3") (pintype "bidirectional"))
      (node (ref "J1") (pin "2") (pinfunction "+_2") (pintype "bidirectional"))
      (node (ref "R6") (pin "P$2") (pinfunction "2_P$2") (pintype "passive"))
      (node (ref "U$4") (pin "6") (pinfunction "IN2_6") (pintype "bidirectional"))
    )
    (net (code "65") (name "VBUS") (class "Default")
      (node (ref "C7") (pin "P$2") (pinfunction "2_P$2") (pintype "passive"))
      (node (ref "CHARGE") (pin "A") (pinfunction "A_A") (pintype "passive"))
      (node (ref "F1") (pin "2") (pinfunction "2_2") (pintype "bidirectional"))
      (node (ref "IC3") (pin "4") (pinfunction "VDD_4") (pintype "power_in"))
      (node (ref "U$4") (pin "8") (pinfunction "IN1_8") (pintype "bidirectional"))
    )
    (net (code "66") (name "VCC") (class "Default")
      (node (ref "C10") (pin "P$2") (pinfunction "2_P$2") (pintype "passive"))
      (node (ref "C11") (pin "P$2") (pinfunction "2_P$2") (pintype "passive"))
      (node (ref "C3") (pin "P$1") (pinfunction "1_P$1") (pintype "passive"))
      (node (ref "C4") (pin "P$1") (pinfunction "1_P$1") (pintype "passive"))
      (node (ref "C9") (pin "P$2") (pinfunction "2_P$2") (pintype "passive"))
      (node (ref "CH340G") (pin "16") (pinfunction "VCC_16") (pintype "bidirectional"))
      (node (ref "CH340G") (pin "4") (pinfunction "V3_4") (pintype "bidirectional"))
      (node (ref "IC1") (pin "16") (pinfunction "VDD_16") (pintype "power_in"))
      (node (ref "JP2") (pin "P$2") (pinfunction "2_P$2") (pintype "passive"))
      (node (ref "LED1") (pin "4") (pinfunction "A_4") (pintype "passive"))
      (node (ref "LED2") (pin "4") (pinfunction "A_4") (pintype "passive"))
      (node (ref "LED3") (pin "4") (pinfunction "A_4") (pintype "passive"))
      (node (ref "LED4") (pin "4") (pinfunction "A_4") (pintype "passive"))
      (node (ref "R1") (pin "P$2") (pinfunction "2_P$2") (pintype "passive"))
      (node (ref "R12") (pin "P$1") (pinfunction "1_P$1") (pintype "passive"))
      (node (ref "R13") (pin "P$1") (pinfunction "1_P$1") (pintype "passive"))
      (node (ref "RPU") (pin "1") (pinfunction "1_1") (pintype "passive"))
      (node (ref "RPU") (pin "2") (pinfunction "1_2") (pintype "passive"))
      (node (ref "RPU") (pin "3") (pinfunction "1_3") (pintype "passive"))
      (node (ref "RPU") (pin "4") (pinfunction "1_4") (pintype "passive"))
      (node (ref "U$1") (pin "1") (pinfunction "VDD_1") (pintype "power_in"))
      (node (ref "U$1") (pin "6") (pinfunction "OSC_6") (pintype "passive"))
      (node (ref "U$10") (pin "P$2") (pinfunction "VCC_P$2") (pintype "bidirectional"))
      (node (ref "U$2") (pin "8") (pinfunction "VCC_8") (pintype "bidirectional"))
      (node (ref "U$9") (pin "P$5") (pinfunction "VOUT_P$5") (pintype "bidirectional"))
      (node (ref "U1") (pin "P$4") (pinfunction "VCC_P$4") (pintype "bidirectional"))
      (node (ref "X1") (pin "8") (pinfunction "VCC_8") (pintype "power_in"))
    )
    (net (code "67") (name "VREG_IN") (class "Default")
      (node (ref "C2") (pin "P$1") (pinfunction "1_P$1") (pintype "passive"))
      (node (ref "S2") (pin "1") (pinfunction "O_1") (pintype "passive"))
      (node (ref "U$4") (pin "7") (pinfunction "OUT_7") (pintype "bidirectional"))
      (node (ref "U$9") (pin "P$1") (pinfunction "VIN_P$1") (pintype "bidirectional"))
    )
    (net (code "68") (name "unconnected-(CH340G-CTS-Pad9)") (class "Default")
      (node (ref "CH340G") (pin "9") (pinfunction "CTS_9") (pintype "bidirectional"))
    )
    (net (code "69") (name "unconnected-(CH340G-DCD-Pad12)") (class "Default")
      (node (ref "CH340G") (pin "12") (pinfunction "DCD_12") (pintype "bidirectional"))
    )
    (net (code "70") (name "unconnected-(CH340G-DSR-Pad10)") (class "Default")
      (node (ref "CH340G") (pin "10") (pinfunction "DSR_10") (pintype "bidirectional"))
    )
    (net (code "71") (name "unconnected-(CH340G-RI-Pad11)") (class "Default")
      (node (ref "CH340G") (pin "11") (pinfunction "RI_11") (pintype "bidirectional"))
    )
    (net (code "72") (name "unconnected-(CH340G-RS232-Pad15)") (class "Default")
      (node (ref "CH340G") (pin "15") (pinfunction "RS232_15") (pintype "bidirectional"))
    )
    (net (code "73") (name "unconnected-(IC1-~{INT}-Pad13)") (class "Default")
      (node (ref "IC1") (pin "13") (pinfunction "~{INT}_13") (pintype "output"))
    )
    (net (code "74") (name "unconnected-(J1-PAD1-PadNC1)") (class "Default")
      (node (ref "J1") (pin "NC1") (pinfunction "PAD1_NC1") (pintype "bidirectional"))
    )
    (net (code "75") (name "unconnected-(J1-PAD2-PadNC2)") (class "Default")
      (node (ref "J1") (pin "NC2") (pinfunction "PAD2_NC2") (pintype "bidirectional"))
    )
    (net (code "76") (name "unconnected-(JP1-ID-PadID1)") (class "Default")
      (node (ref "JP1") (pin "ID1") (pinfunction "ID_ID1") (pintype "bidirectional"))
    )
    (net (code "77") (name "unconnected-(U$4-STAT-Pad1)") (class "Default")
      (node (ref "U$4") (pin "1") (pinfunction "STAT_1") (pintype "bidirectional"))
    )
    (net (code "78") (name "unconnected-(U1-NC-PadP$1)") (class "Default")
      (node (ref "U1") (pin "P$1") (pinfunction "NC_P$1") (pintype "bidirectional"))
    )
    (net (code "79") (name "unconnected-(U1-RSV-PadP$8)") (class "Default")
      (node (ref "U1") (pin "P$8") (pinfunction "RSV_P$8") (pintype "bidirectional"))
    )
  )
)
